# 50_Shot_CPU_V0_0.net
KiCad netlist of a schematic drawn in EAGLE
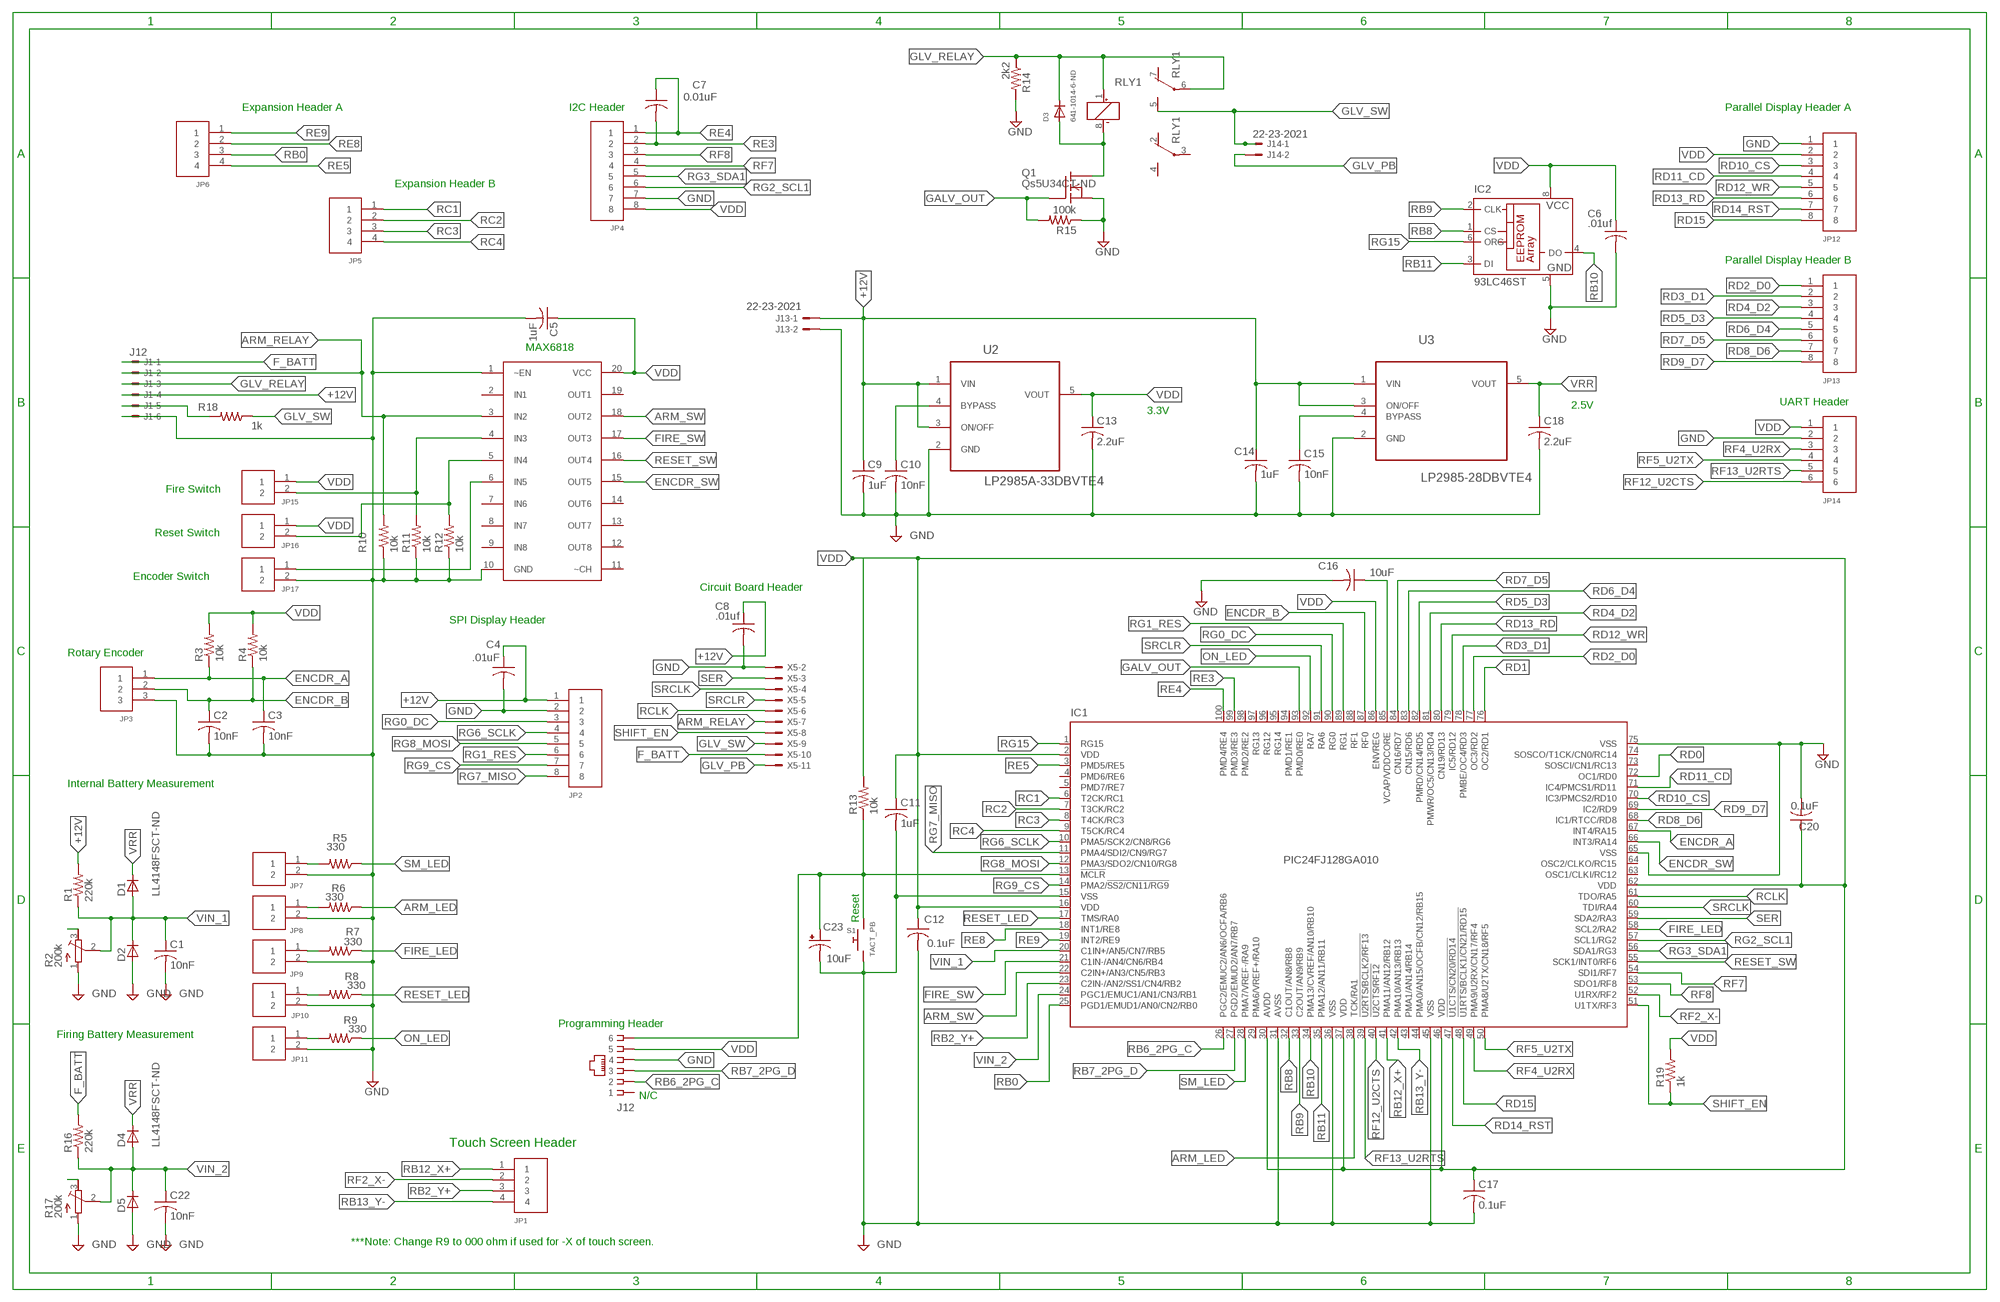
[diagram p0: schematic, sheet 1]

(export (version "E")
  (design (tool "Eeschema 10.0.6"))
  (components
    (comp (ref "C1")
      (value "10nF")
      (footprint "eagle-import:C0805")
      (libsource (lib "eagle-import") (part "C-USC0805"))
    )
    (comp (ref "C2")
      (value "10nF")
      (footprint "eagle-import:C0805")
      (libsource (lib "eagle-import") (part "C-USC0805"))
    )
    (comp (ref "C3")
      (value "10nF")
      (footprint "eagle-import:C0805")
      (libsource (lib "eagle-import") (part "C-USC0805"))
    )
    (comp (ref "C4")
      (value ".01uF")
      (footprint "eagle-import:C0805")
      (libsource (lib "eagle-import") (part "C-USC0805"))
    )
    (comp (ref "C5")
      (value "1uF")
      (footprint "eagle-import:C0805")
      (libsource (lib "eagle-import") (part "C-USC0805"))
    )
    (comp (ref "C6")
      (value ".01uf")
      (footprint "eagle-import:C0805")
      (libsource (lib "eagle-import") (part "C-USC0805"))
    )
    (comp (ref "C7")
      (value "0.01uF")
      (footprint "eagle-import:C0805")
      (libsource (lib "eagle-import") (part "C-USC0805"))
    )
    (comp (ref "C8")
      (value ".01uf")
      (footprint "eagle-import:C0805")
      (libsource (lib "eagle-import") (part "C-USC0805"))
    )
    (comp (ref "C9")
      (value "1uF")
      (footprint "eagle-import:C0805")
      (libsource (lib "eagle-import") (part "C-USC0805"))
    )
    (comp (ref "C10")
      (value "10nF")
      (footprint "eagle-import:C0805")
      (libsource (lib "eagle-import") (part "C-USC0805"))
    )
    (comp (ref "C11")
      (value "1uF")
      (footprint "eagle-import:C0805")
      (libsource (lib "eagle-import") (part "C-USC0805"))
    )
    (comp (ref "C12")
      (value "0.1uF")
      (footprint "eagle-import:C0805")
      (libsource (lib "eagle-import") (part "C-USC0805"))
    )
    (comp (ref "C13")
      (value "2.2uF")
      (footprint "eagle-import:C0805")
      (libsource (lib "eagle-import") (part "C-USC0805"))
    )
    (comp (ref "C14")
      (value "1uF")
      (footprint "eagle-import:C0805")
      (libsource (lib "eagle-import") (part "C-USC0805"))
    )
    (comp (ref "C15")
      (value "10nF")
      (footprint "eagle-import:C0805")
      (libsource (lib "eagle-import") (part "C-USC0805"))
    )
    (comp (ref "C16")
      (value "10uF")
      (footprint "eagle-import:C0805")
      (libsource (lib "eagle-import") (part "C-USC0805"))
    )
    (comp (ref "C17")
      (value "0.1uF")
      (footprint "eagle-import:C0805")
      (libsource (lib "eagle-import") (part "C-USC0805"))
    )
    (comp (ref "C18")
      (value "2.2uF")
      (footprint "eagle-import:C0805")
      (libsource (lib "eagle-import") (part "C-USC0805"))
    )
    (comp (ref "C20")
      (value "0.1uF")
      (footprint "eagle-import:C0805")
      (libsource (lib "eagle-import") (part "C-USC0805"))
    )
    (comp (ref "C22")
      (value "10nF")
      (footprint "eagle-import:C0805")
      (libsource (lib "eagle-import") (part "C-USC0805"))
    )
    (comp (ref "C23")
      (value "10uF")
      (footprint "eagle-import:CAP3X3")
      (libsource (lib "eagle-import") (part "CAP3X3"))
    )
    (comp (ref "D1")
      (value "LL4148FSCT-ND")
      (footprint "eagle-import:SOD80")
      (libsource (lib "eagle-import") (part "D-SOD-80"))
    )
    (comp (ref "D2")
      (value "LL4148FSCT-ND")
      (footprint "eagle-import:SOD80")
      (libsource (lib "eagle-import") (part "D-SOD-80"))
    )
    (comp (ref "D3")
      (value "641-1014-6-ND")
      (footprint "eagle-import:SOD-123")
      (libsource (lib "eagle-import") (part "DIODESOD-123"))
    )
    (comp (ref "D4")
      (value "LL4148FSCT-ND")
      (footprint "eagle-import:SOD80")
      (libsource (lib "eagle-import") (part "D-SOD-80"))
    )
    (comp (ref "D5")
      (value "LL4148FSCT-ND")
      (footprint "eagle-import:SOD80")
      (libsource (lib "eagle-import") (part "D-SOD-80"))
    )
    (comp (ref "IC1")
      (value "PIC24FJ128GA010")
      (footprint "eagle-import:TQFP100-14X14")
      (fields (field (name "MPN") "PIC24FJ128GA010-I/PT"))
      (libsource (lib "eagle-import") (part "PIC24FJGA010128"))
    )
    (comp (ref "IC2")
      (value "93LC46ST")
      (footprint "eagle-import:TSSOP8")
      (fields (field (name "MF") "MICROCHIP") (field (name "MPN") "93LC46C-I/ST"))
      (libsource (lib "eagle-import") (part "93STLC46"))
    )
    (comp (ref "J1")
      (value "J12")
      (footprint "eagle-import:22-23-2061")
      (fields (field (name "MF") "MOLEX") (field (name "MPN") "22-23-2061"))
      (libsource (lib "eagle-import") (part "22-23-2061"))
    )
    (comp (ref "J12")
      (value "A311422_nd")
      (footprint "eagle-import:RJ11-NO_SHIELD")
      (libsource (lib "eagle-import") (part "RJ_25"))
    )
    (comp (ref "J13")
      (value "22-23-2021")
      (footprint "eagle-import:22-23-2021")
      (fields (field (name "MF") "MOLEX"))
      (libsource (lib "eagle-import") (part "22-23-2021"))
    )
    (comp (ref "J14")
      (value "22-23-2021")
      (footprint "eagle-import:22-23-2021")
      (fields (field (name "MF") "MOLEX"))
      (libsource (lib "eagle-import") (part "22-23-2021"))
    )
    (comp (ref "JP1")
      (value "SHERLOCK_4PIN_RGT")
      (footprint "eagle-import:SHERLOCK_4PIN_RGT")
      (libsource (lib "eagle-import") (part "SHERLOCK_4PIN_RGT"))
    )
    (comp (ref "JP2")
      (value "SHERLOCK_8PIN_RGT")
      (footprint "eagle-import:SHERLOCK_8PIN-RGT")
      (libsource (lib "eagle-import") (part "SHERLOCK_8PIN_RGT"))
    )
    (comp (ref "JP3")
      (value "SHERLOCK_3PIN_RGT")
      (footprint "eagle-import:SHERLOCK_3PIN_RGT")
      (libsource (lib "eagle-import") (part "SHERLOCK_3PIN_RGT"))
    )
    (comp (ref "JP4")
      (value "SHERLOCK_8PIN_RGT")
      (footprint "eagle-import:SHERLOCK_8PIN-RGT")
      (libsource (lib "eagle-import") (part "SHERLOCK_8PIN_RGT"))
    )
    (comp (ref "JP5")
      (value "SHERLOCK_4PIN_RGT")
      (footprint "eagle-import:SHERLOCK_4PIN_RGT")
      (libsource (lib "eagle-import") (part "SHERLOCK_4PIN_RGT"))
    )
    (comp (ref "JP6")
      (value "SHERLOCK_4PIN_RGT")
      (footprint "eagle-import:SHERLOCK_4PIN_RGT")
      (libsource (lib "eagle-import") (part "SHERLOCK_4PIN_RGT"))
    )
    (comp (ref "JP7")
      (value "SHERLOCK_2PIN_RGT")
      (footprint "eagle-import:SHERLOCK_2PIN_RGT")
      (libsource (lib "eagle-import") (part "SHERLOCK_2PIN_RGT"))
    )
    (comp (ref "JP8")
      (value "SHERLOCK_2PIN_RGT")
      (footprint "eagle-import:SHERLOCK_2PIN_RGT")
      (libsource (lib "eagle-import") (part "SHERLOCK_2PIN_RGT"))
    )
    (comp (ref "JP9")
      (value "SHERLOCK_2PIN_RGT")
      (footprint "eagle-import:SHERLOCK_2PIN_RGT")
      (libsource (lib "eagle-import") (part "SHERLOCK_2PIN_RGT"))
    )
    (comp (ref "JP10")
      (value "SHERLOCK_2PIN_RGT")
      (footprint "eagle-import:SHERLOCK_2PIN_RGT")
      (libsource (lib "eagle-import") (part "SHERLOCK_2PIN_RGT"))
    )
    (comp (ref "JP11")
      (value "SHERLOCK_2PIN_RGT")
      (footprint "eagle-import:SHERLOCK_2PIN_RGT")
      (libsource (lib "eagle-import") (part "SHERLOCK_2PIN_RGT"))
    )
    (comp (ref "JP12")
      (value "SHERLOCK_8PIN_RGT")
      (footprint "eagle-import:SHERLOCK_8PIN-RGT")
      (libsource (lib "eagle-import") (part "SHERLOCK_8PIN_RGT"))
    )
    (comp (ref "JP13")
      (value "SHERLOCK_8PIN_RGT")
      (footprint "eagle-import:SHERLOCK_8PIN-RGT")
      (libsource (lib "eagle-import") (part "SHERLOCK_8PIN_RGT"))
    )
    (comp (ref "JP14")
      (value "SHERLOCK_6PIN_RGT")
      (footprint "eagle-import:SHERLOCK_6PIN_RGT")
      (libsource (lib "eagle-import") (part "SHERLOCK_6PIN_RGT"))
    )
    (comp (ref "JP15")
      (value "SHERLOCK_2PIN_RGT")
      (footprint "eagle-import:SHERLOCK_2PIN_RGT")
      (libsource (lib "eagle-import") (part "SHERLOCK_2PIN_RGT"))
    )
    (comp (ref "JP16")
      (value "SHERLOCK_2PIN_RGT")
      (footprint "eagle-import:SHERLOCK_2PIN_RGT")
      (libsource (lib "eagle-import") (part "SHERLOCK_2PIN_RGT"))
    )
    (comp (ref "JP17")
      (value "SHERLOCK_2PIN_RGT")
      (footprint "eagle-import:SHERLOCK_2PIN_RGT")
      (libsource (lib "eagle-import") (part "SHERLOCK_2PIN_RGT"))
    )
    (comp (ref "Q1")
      (value "Qs5U34CT-ND")
      (footprint "eagle-import:SOT23-5L")
      (libsource (lib "eagle-import") (part "QS5U34CT-ND_MOSFET_N_CHANNEL"))
    )
    (comp (ref "R1")
      (value "220k")
      (footprint "eagle-import:M0805")
      (libsource (lib "eagle-import") (part "R-US_M0805"))
    )
    (comp (ref "R2")
      (value "200k")
      (footprint "eagle-import:RTRIM3224X")
      (libsource (lib "eagle-import") (part "R-TRIMM3224X"))
    )
    (comp (ref "R3")
      (value "10k")
      (footprint "eagle-import:M0805")
      (libsource (lib "eagle-import") (part "R-US_M0805"))
    )
    (comp (ref "R4")
      (value "10k")
      (footprint "eagle-import:M0805")
      (libsource (lib "eagle-import") (part "R-US_M0805"))
    )
    (comp (ref "R5")
      (value "330")
      (footprint "eagle-import:M0805")
      (libsource (lib "eagle-import") (part "R-US_M0805"))
    )
    (comp (ref "R6")
      (value "330")
      (footprint "eagle-import:M0805")
      (libsource (lib "eagle-import") (part "R-US_M0805"))
    )
    (comp (ref "R7")
      (value "330")
      (footprint "eagle-import:M0805")
      (libsource (lib "eagle-import") (part "R-US_M0805"))
    )
    (comp (ref "R8")
      (value "330")
      (footprint "eagle-import:M0805")
      (libsource (lib "eagle-import") (part "R-US_M0805"))
    )
    (comp (ref "R9")
      (value "330")
      (footprint "eagle-import:M0805")
      (libsource (lib "eagle-import") (part "R-US_M0805"))
    )
    (comp (ref "R10")
      (value "10k")
      (footprint "eagle-import:M0805")
      (libsource (lib "eagle-import") (part "R-US_M0805"))
    )
    (comp (ref "R11")
      (value "10k")
      (footprint "eagle-import:M0805")
      (libsource (lib "eagle-import") (part "R-US_M0805"))
    )
    (comp (ref "R12")
      (value "10k")
      (footprint "eagle-import:M0805")
      (libsource (lib "eagle-import") (part "R-US_M0805"))
    )
    (comp (ref "R13")
      (value "10k")
      (footprint "eagle-import:M0805")
      (libsource (lib "eagle-import") (part "rcl-2_R-US_M0805"))
    )
    (comp (ref "R14")
      (value "2k2")
      (footprint "eagle-import:M0805")
      (libsource (lib "eagle-import") (part "R-US_M0805"))
    )
    (comp (ref "R15")
      (value "100k")
      (footprint "eagle-import:M0805")
      (libsource (lib "eagle-import") (part "R-US_M0805"))
    )
    (comp (ref "R16")
      (value "220k")
      (footprint "eagle-import:M0805")
      (libsource (lib "eagle-import") (part "R-US_M0805"))
    )
    (comp (ref "R17")
      (value "200k")
      (footprint "eagle-import:RTRIM3224X")
      (libsource (lib "eagle-import") (part "R-TRIMM3224X"))
    )
    (comp (ref "R18")
      (value "1k")
      (footprint "eagle-import:M0805")
      (libsource (lib "eagle-import") (part "R-US_M0805"))
    )
    (comp (ref "R19")
      (value "1k")
      (footprint "eagle-import:M0805")
      (libsource (lib "eagle-import") (part "rcl-2_R-US_M0805"))
    )
    (comp (ref "RLY1")
      (value "OMRON")
      (footprint "eagle-import:OMRONG6S")
      (libsource (lib "eagle-import") (part "OMRON"))
    )
    (comp (ref "S1")
      (value "TACT_PB")
      (footprint "eagle-import:PUSHBUTTON_SMD_SJ")
      (libsource (lib "eagle-import") (part "TACT_PB"))
    )
    (comp (ref "U1")
      (value "MAX6818")
      (footprint "eagle-import:SSOP20")
      (libsource (lib "eagle-import") (part "MAX6818"))
    )
    (comp (ref "U2")
      (value "LP2985A-33DBVTE4")
      (footprint "eagle-import:SOT95P280X145-5N")
      (libsource (lib "eagle-import") (part "LP2985A-33DBVTE4"))
    )
    (comp (ref "U3")
      (value "LP2985-28DBVTE4")
      (footprint "eagle-import:SOT95P280X145-5N")
      (libsource (lib "eagle-import") (part "LP2985-28DBVTE4"))
    )
    (comp (ref "X5")
      (value "22-23-2111")
      (footprint "eagle-import:22-23-2111")
      (fields (field (name "MF") "MOLEX"))
      (libsource (lib "eagle-import") (part "22-23-2111"))
    )
  )
  (nets
    (net (code "1") (name "+12V") (class "Default")
      (node (ref "C14") (pin "1") (pinfunction "1_1") (pintype "passive"))
      (node (ref "C4") (pin "1") (pinfunction "1_1") (pintype "passive"))
      (node (ref "C8") (pin "1") (pinfunction "1_1") (pintype "passive"))
      (node (ref "C9") (pin "1") (pinfunction "1_1") (pintype "passive"))
      (node (ref "J1") (pin "4") (pinfunction "S_4") (pintype "passive"))
      (node (ref "J13") (pin "1") (pinfunction "S_1") (pintype "passive"))
      (node (ref "JP2") (pin "1") (pinfunction "1_1") (pintype "bidirectional"))
      (node (ref "R1") (pin "2") (pinfunction "2_2") (pintype "passive"))
      (node (ref "U2") (pin "1") (pinfunction "VIN_1") (pintype "power_in"))
      (node (ref "U2") (pin "3") (pinfunction "ON/OFF_3") (pintype "input"))
      (node (ref "U3") (pin "1") (pinfunction "VIN_1") (pintype "power_in"))
      (node (ref "U3") (pin "3") (pinfunction "ON/OFF_3") (pintype "input"))
    )
    (net (code "2") (name "ARM_LED") (class "Default")
      (node (ref "IC1") (pin "38") (pinfunction "TCK/RA1_38") (pintype "bidirectional"))
      (node (ref "R6") (pin "1") (pinfunction "1_1") (pintype "passive"))
    )
    (net (code "3") (name "ARM_RELAY") (class "Default")
      (node (ref "J1") (pin "2") (pinfunction "S_2") (pintype "passive"))
      (node (ref "R10") (pin "2") (pinfunction "2_2") (pintype "passive"))
      (node (ref "U1") (pin "3") (pinfunction "IN2_3") (pintype "bidirectional"))
      (node (ref "X5") (pin "7") (pinfunction "S_7") (pintype "passive"))
    )
    (net (code "4") (name "ARM_SW") (class "Default")
      (node (ref "IC1") (pin "22") (pinfunction "C2IN+/AN3/CN5/RB3_22") (pintype "bidirectional"))
      (node (ref "U1") (pin "18") (pinfunction "OUT2_18") (pintype "output"))
    )
    (net (code "5") (name "ENCDR_A") (class "Default")
      (node (ref "C3") (pin "1") (pinfunction "1_1") (pintype "passive"))
      (node (ref "IC1") (pin "67") (pinfunction "INT4/RA15_67") (pintype "bidirectional"))
      (node (ref "JP3") (pin "1") (pinfunction "1_1") (pintype "bidirectional"))
      (node (ref "R3") (pin "1") (pinfunction "1_1") (pintype "passive"))
    )
    (net (code "6") (name "ENCDR_B") (class "Default")
      (node (ref "C2") (pin "1") (pinfunction "1_1") (pintype "passive"))
      (node (ref "IC1") (pin "87") (pinfunction "RF0_87") (pintype "bidirectional"))
      (node (ref "JP3") (pin "2") (pinfunction "2_2") (pintype "bidirectional"))
      (node (ref "R4") (pin "1") (pinfunction "1_1") (pintype "passive"))
    )
    (net (code "7") (name "ENCDR_SW") (class "Default")
      (node (ref "IC1") (pin "66") (pinfunction "INT3/RA14_66") (pintype "bidirectional"))
      (node (ref "U1") (pin "15") (pinfunction "OUT5_15") (pintype "output"))
    )
    (net (code "8") (name "FIRE_LED") (class "Default")
      (node (ref "IC1") (pin "58") (pinfunction "SCL2/RA2_58") (pintype "bidirectional"))
      (node (ref "R7") (pin "1") (pinfunction "1_1") (pintype "passive"))
    )
    (net (code "9") (name "FIRE_SW") (class "Default")
      (node (ref "IC1") (pin "21") (pinfunction "C1IN-/AN4/CN6/RB4_21") (pintype "bidirectional"))
      (node (ref "U1") (pin "17") (pinfunction "OUT3_17") (pintype "output"))
    )
    (net (code "10") (name "F_BATT") (class "Default")
      (node (ref "J1") (pin "1") (pinfunction "S_1") (pintype "passive"))
      (node (ref "R16") (pin "2") (pinfunction "2_2") (pintype "passive"))
      (node (ref "X5") (pin "10") (pinfunction "S_10") (pintype "passive"))
    )
    (net (code "11") (name "GALV_OUT") (class "Default")
      (node (ref "IC1") (pin "93") (pinfunction "PMD0/RE0_93") (pintype "bidirectional"))
      (node (ref "Q1") (pin "1") (pinfunction "G_1") (pintype "passive"))
      (node (ref "R15") (pin "2") (pinfunction "2_2") (pintype "passive"))
    )
    (net (code "12") (name "GLV_PB") (class "Default")
      (node (ref "J14") (pin "2") (pinfunction "S_2") (pintype "passive"))
      (node (ref "X5") (pin "11") (pinfunction "S_11") (pintype "passive"))
    )
    (net (code "13") (name "GLV_RELAY") (class "Default")
      (node (ref "D3") (pin "C") (pinfunction "C_C") (pintype "passive"))
      (node (ref "J1") (pin "3") (pinfunction "S_3") (pintype "passive"))
      (node (ref "R14") (pin "1") (pinfunction "1_1") (pintype "passive"))
      (node (ref "RLY1") (pin "1") (pinfunction "+_1") (pintype "passive"))
      (node (ref "RLY1") (pin "6") (pinfunction "P_6") (pintype "passive"))
    )
    (net (code "14") (name "GLV_SW") (class "Default")
      (node (ref "J14") (pin "1") (pinfunction "S_1") (pintype "passive"))
      (node (ref "R18") (pin "1") (pinfunction "1_1") (pintype "passive"))
      (node (ref "RLY1") (pin "5") (pinfunction "S_5") (pintype "passive"))
      (node (ref "X5") (pin "9") (pinfunction "S_9") (pintype "passive"))
    )
    (net (code "15") (name "GND") (class "Default")
      (node (ref "C1") (pin "2") (pinfunction "2_2") (pintype "passive"))
      (node (ref "C10") (pin "2") (pinfunction "2_2") (pintype "passive"))
      (node (ref "C11") (pin "2") (pinfunction "2_2") (pintype "passive"))
      (node (ref "C12") (pin "2") (pinfunction "2_2") (pintype "passive"))
      (node (ref "C13") (pin "2") (pinfunction "2_2") (pintype "passive"))
      (node (ref "C14") (pin "2") (pinfunction "2_2") (pintype "passive"))
      (node (ref "C15") (pin "2") (pinfunction "2_2") (pintype "passive"))
      (node (ref "C16") (pin "2") (pinfunction "2_2") (pintype "passive"))
      (node (ref "C17") (pin "2") (pinfunction "2_2") (pintype "passive"))
      (node (ref "C18") (pin "2") (pinfunction "2_2") (pintype "passive"))
      (node (ref "C2") (pin "2") (pinfunction "2_2") (pintype "passive"))
      (node (ref "C20") (pin "2") (pinfunction "2_2") (pintype "passive"))
      (node (ref "C22") (pin "2") (pinfunction "2_2") (pintype "passive"))
      (node (ref "C23") (pin "-") (pinfunction "-_-") (pintype "passive"))
      (node (ref "C3") (pin "2") (pinfunction "2_2") (pintype "passive"))
      (node (ref "C4") (pin "2") (pinfunction "2_2") (pintype "passive"))
      (node (ref "C5") (pin "2") (pinfunction "2_2") (pintype "passive"))
      (node (ref "C6") (pin "2") (pinfunction "2_2") (pintype "passive"))
      (node (ref "C8") (pin "2") (pinfunction "2_2") (pintype "passive"))
      (node (ref "C9") (pin "2") (pinfunction "2_2") (pintype "passive"))
      (node (ref "D2") (pin "2") (pinfunction "A_2") (pintype "passive"))
      (node (ref "D5") (pin "2") (pinfunction "A_2") (pintype "passive"))
      (node (ref "IC1") (pin "15") (pinfunction "VSS_15") (pintype "power_in"))
      (node (ref "IC1") (pin "31") (pinfunction "AVSS_31") (pintype "power_in"))
      (node (ref "IC1") (pin "36") (pinfunction "VSS_36") (pintype "power_in"))
      (node (ref "IC1") (pin "45") (pinfunction "VSS_45") (pintype "power_in"))
      (node (ref "IC1") (pin "65") (pinfunction "VSS_65") (pintype "power_in"))
      (node (ref "IC1") (pin "75") (pinfunction "VSS_75") (pintype "power_in"))
      (node (ref "IC2") (pin "5") (pinfunction "GND_5") (pintype "power_in"))
      (node (ref "J1") (pin "6") (pinfunction "S_6") (pintype "passive"))
      (node (ref "J12") (pin "4") (pinfunction "4_4") (pintype "passive"))
      (node (ref "J13") (pin "2") (pinfunction "S_2") (pintype "passive"))
      (node (ref "JP10") (pin "2") (pinfunction "2_2") (pintype "bidirectional"))
      (node (ref "JP11") (pin "2") (pinfunction "2_2") (pintype "bidirectional"))
      (node (ref "JP12") (pin "1") (pinfunction "1_1") (pintype "bidirectional"))
      (node (ref "JP14") (pin "2") (pinfunction "2_2") (pintype "bidirectional"))
      (node (ref "JP17") (pin "2") (pinfunction "2_2") (pintype "bidirectional"))
      (node (ref "JP2") (pin "2") (pinfunction "2_2") (pintype "bidirectional"))
      (node (ref "JP3") (pin "3") (pinfunction "3_3") (pintype "bidirectional"))
      (node (ref "JP4") (pin "7") (pinfunction "7_7") (pintype "bidirectional"))
      (node (ref "JP7") (pin "2") (pinfunction "2_2") (pintype "bidirectional"))
      (node (ref "JP8") (pin "2") (pinfunction "2_2") (pintype "bidirectional"))
      (node (ref "JP9") (pin "2") (pinfunction "2_2") (pintype "bidirectional"))
      (node (ref "Q1") (pin "2") (pinfunction "S_2") (pintype "passive"))
      (node (ref "R10") (pin "1") (pinfunction "1_1") (pintype "passive"))
      (node (ref "R11") (pin "1") (pinfunction "1_1") (pintype "passive"))
      (node (ref "R12") (pin "1") (pinfunction "1_1") (pintype "passive"))
      (node (ref "R14") (pin "2") (pinfunction "2_2") (pintype "passive"))
      (node (ref "R15") (pin "1") (pinfunction "1_1") (pintype "passive"))
      (node (ref "R17") (pin "1") (pinfunction "A_1") (pintype "passive"))
      (node (ref "R2") (pin "1") (pinfunction "A_1") (pintype "passive"))
      (node (ref "S1") (pin "1") (pinfunction "1_1") (pintype "passive"))
      (node (ref "S1") (pin "2") (pinfunction "1_2") (pintype "passive"))
      (node (ref "U1") (pin "1") (pinfunction "~{EN}_1") (pintype "bidirectional"))
      (node (ref "U1") (pin "10") (pinfunction "GND_10") (pintype "power_in"))
      (node (ref "U2") (pin "2") (pinfunction "GND_2") (pintype "passive"))
      (node (ref "U3") (pin "2") (pinfunction "GND_2") (pintype "passive"))
      (node (ref "X5") (pin "2") (pinfunction "S_2") (pintype "passive"))
    )
    (net (code "16") (name "Net-(IC1-VCAP{slash}VDDCORE)") (class "Default")
      (node (ref "C16") (pin "1") (pinfunction "1_1") (pintype "passive"))
      (node (ref "IC1") (pin "85") (pinfunction "VCAP/VDDCORE_85") (pintype "bidirectional"))
    )
    (net (code "17") (name "Net-(IC1-~{MCLR})") (class "Default")
      (node (ref "C23") (pin "+") (pinfunction "+_+") (pintype "passive"))
      (node (ref "IC1") (pin "13") (pinfunction "~{MCLR}_13") (pintype "bidirectional"))
      (node (ref "J12") (pin "6") (pinfunction "6_6") (pintype "passive"))
      (node (ref "R13") (pin "1") (pinfunction "1_1") (pintype "passive"))
      (node (ref "S1") (pin "3") (pinfunction "2_3") (pintype "passive"))
      (node (ref "S1") (pin "4") (pinfunction "2_4") (pintype "passive"))
    )
    (net (code "18") (name "Net-(J1E-S)") (class "Default")
      (node (ref "J1") (pin "5") (pinfunction "S_5") (pintype "passive"))
      (node (ref "R18") (pin "2") (pinfunction "2_2") (pintype "passive"))
    )
    (net (code "19") (name "Net-(JP7-Pad1)") (class "Default")
      (node (ref "JP7") (pin "1") (pinfunction "1_1") (pintype "bidirectional"))
      (node (ref "R5") (pin "2") (pinfunction "2_2") (pintype "passive"))
    )
    (net (code "20") (name "Net-(JP8-Pad1)") (class "Default")
      (node (ref "JP8") (pin "1") (pinfunction "1_1") (pintype "bidirectional"))
      (node (ref "R6") (pin "2") (pinfunction "2_2") (pintype "passive"))
    )
    (net (code "21") (name "Net-(JP9-Pad1)") (class "Default")
      (node (ref "JP9") (pin "1") (pinfunction "1_1") (pintype "bidirectional"))
      (node (ref "R7") (pin "2") (pinfunction "2_2") (pintype "passive"))
    )
    (net (code "22") (name "Net-(JP10-Pad1)") (class "Default")
      (node (ref "JP10") (pin "1") (pinfunction "1_1") (pintype "bidirectional"))
      (node (ref "R8") (pin "2") (pinfunction "2_2") (pintype "passive"))
    )
    (net (code "23") (name "Net-(JP11-Pad1)") (class "Default")
      (node (ref "JP11") (pin "1") (pinfunction "1_1") (pintype "bidirectional"))
      (node (ref "R9") (pin "2") (pinfunction "2_2") (pintype "passive"))
    )
    (net (code "24") (name "Net-(Q1-D)") (class "Default")
      (node (ref "D3") (pin "A") (pinfunction "A_A") (pintype "passive"))
      (node (ref "Q1") (pin "5") (pinfunction "D_5") (pintype "passive"))
      (node (ref "RLY1") (pin "8") (pinfunction "-_8") (pintype "passive"))
    )
    (net (code "25") (name "Net-(U1-IN3)") (class "Default")
      (node (ref "JP15") (pin "2") (pinfunction "2_2") (pintype "bidirectional"))
      (node (ref "R11") (pin "2") (pinfunction "2_2") (pintype "passive"))
      (node (ref "U1") (pin "4") (pinfunction "IN3_4") (pintype "bidirectional"))
    )
    (net (code "26") (name "Net-(U1-IN4)") (class "Default")
      (node (ref "JP16") (pin "2") (pinfunction "2_2") (pintype "bidirectional"))
      (node (ref "R12") (pin "2") (pinfunction "2_2") (pintype "passive"))
      (node (ref "U1") (pin "5") (pinfunction "IN4_5") (pintype "bidirectional"))
    )
    (net (code "27") (name "Net-(U1-IN5)") (class "Default")
      (node (ref "JP17") (pin "1") (pinfunction "1_1") (pintype "bidirectional"))
      (node (ref "U1") (pin "6") (pinfunction "IN5_6") (pintype "bidirectional"))
    )
    (net (code "28") (name "Net-(U2-BYPASS)") (class "Default")
      (node (ref "C10") (pin "1") (pinfunction "1_1") (pintype "passive"))
      (node (ref "U2") (pin "4") (pinfunction "BYPASS_4") (pintype "input"))
    )
    (net (code "29") (name "Net-(U3-BYPASS)") (class "Default")
      (node (ref "C15") (pin "1") (pinfunction "1_1") (pintype "passive"))
      (node (ref "U3") (pin "4") (pinfunction "BYPASS_4") (pintype "input"))
    )
    (net (code "30") (name "ON_LED") (class "Default")
      (node (ref "IC1") (pin "92") (pinfunction "RA7_92") (pintype "bidirectional"))
      (node (ref "R9") (pin "1") (pinfunction "1_1") (pintype "passive"))
    )
    (net (code "31") (name "RB0") (class "Default")
      (node (ref "IC1") (pin "25") (pinfunction "PGD1/EMUD1/AN0/CN2/RB0_25") (pintype "bidirectional"))
      (node (ref "JP6") (pin "3") (pinfunction "3_3") (pintype "bidirectional"))
    )
    (net (code "32") (name "RB2_Y+") (class "Default")
      (node (ref "IC1") (pin "23") (pinfunction "C2IN-/AN2/SS1/CN4/RB2_23") (pintype "bidirectional"))
      (node (ref "JP1") (pin "3") (pinfunction "3_3") (pintype "bidirectional"))
    )
    (net (code "33") (name "RB6_2PG_C") (class "Default")
      (node (ref "IC1") (pin "26") (pinfunction "PGC2/EMUC2/AN6/OCFA/RB6_26") (pintype "bidirectional"))
      (node (ref "J12") (pin "2") (pinfunction "2_2") (pintype "passive"))
    )
    (net (code "34") (name "RB7_2PG_D") (class "Default")
      (node (ref "IC1") (pin "27") (pinfunction "PGD2/EMUD2/AN7/RB7_27") (pintype "bidirectional"))
      (node (ref "J12") (pin "3") (pinfunction "3_3") (pintype "passive"))
    )
    (net (code "35") (name "RB8") (class "Default")
      (node (ref "IC1") (pin "32") (pinfunction "C1OUT/AN8/RB8_32") (pintype "bidirectional"))
      (node (ref "IC2") (pin "1") (pinfunction "CS_1") (pintype "input"))
    )
    (net (code "36") (name "RB9") (class "Default")
      (node (ref "IC1") (pin "33") (pinfunction "C2OUT/AN9/RB9_33") (pintype "bidirectional"))
      (node (ref "IC2") (pin "2") (pinfunction "CLK_2") (pintype "input"))
    )
    (net (code "37") (name "RB10") (class "Default")
      (node (ref "IC1") (pin "34") (pinfunction "PMA13/CVREF/AN10/RB10_34") (pintype "bidirectional"))
      (node (ref "IC2") (pin "4") (pinfunction "DO_4") (pintype "tri_state"))
    )
    (net (code "38") (name "RB11") (class "Default")
      (node (ref "IC1") (pin "35") (pinfunction "PMA12/AN11/RB11_35") (pintype "bidirectional"))
      (node (ref "IC2") (pin "3") (pinfunction "DI_3") (pintype "input"))
    )
    (net (code "39") (name "RB12_X+") (class "Default")
      (node (ref "IC1") (pin "41") (pinfunction "PMA11/AN12/RB12_41") (pintype "bidirectional"))
      (node (ref "JP1") (pin "1") (pinfunction "1_1") (pintype "bidirectional"))
    )
    (net (code "40") (name "RB13_Y-") (class "Default")
      (node (ref "IC1") (pin "42") (pinfunction "PMA10/AN13/RB13_42") (pintype "bidirectional"))
      (node (ref "JP1") (pin "4") (pinfunction "4_4") (pintype "bidirectional"))
    )
    (net (code "41") (name "RC1") (class "Default")
      (node (ref "IC1") (pin "6") (pinfunction "T2CK/RC1_6") (pintype "bidirectional"))
      (node (ref "JP5") (pin "1") (pinfunction "1_1") (pintype "bidirectional"))
    )
    (net (code "42") (name "RC2") (class "Default")
      (node (ref "IC1") (pin "7") (pinfunction "T3CK/RC2_7") (pintype "bidirectional"))
      (node (ref "JP5") (pin "2") (pinfunction "2_2") (pintype "bidirectional"))
    )
    (net (code "43") (name "RC3") (class "Default")
      (node (ref "IC1") (pin "8") (pinfunction "T4CK/RC3_8") (pintype "bidirectional"))
      (node (ref "JP5") (pin "3") (pinfunction "3_3") (pintype "bidirectional"))
    )
    (net (code "44") (name "RC4") (class "Default")
      (node (ref "IC1") (pin "9") (pinfunction "T5CK/RC4_9") (pintype "bidirectional"))
      (node (ref "JP5") (pin "4") (pinfunction "4_4") (pintype "bidirectional"))
    )
    (net (code "45") (name "RCLK") (class "Default")
      (node (ref "IC1") (pin "61") (pinfunction "TDO/RA5_61") (pintype "bidirectional"))
      (node (ref "X5") (pin "6") (pinfunction "S_6") (pintype "passive"))
    )
    (net (code "46") (name "RD0") (class "Default")
      (node (ref "IC1") (pin "72") (pinfunction "OC1/RD0_72") (pintype "bidirectional"))
    )
    (net (code "47") (name "RD1") (class "Default")
      (node (ref "IC1") (pin "76") (pinfunction "OC2/RD1_76") (pintype "bidirectional"))
    )
    (net (code "48") (name "RD2_D0") (class "Default")
      (node (ref "IC1") (pin "77") (pinfunction "OC3/RD2_77") (pintype "bidirectional"))
      (node (ref "JP13") (pin "1") (pinfunction "1_1") (pintype "bidirectional"))
    )
    (net (code "49") (name "RD3_D1") (class "Default")
      (node (ref "IC1") (pin "78") (pinfunction "PMBE/OC4/RD3_78") (pintype "bidirectional"))
      (node (ref "JP13") (pin "2") (pinfunction "2_2") (pintype "bidirectional"))
    )
    (net (code "50") (name "RD4_D2") (class "Default")
      (node (ref "IC1") (pin "81") (pinfunction "PMWR/OC5/CN13/RD4_81") (pintype "bidirectional"))
      (node (ref "JP13") (pin "3") (pinfunction "3_3") (pintype "bidirectional"))
    )
    (net (code "51") (name "RD5_D3") (class "Default")
      (node (ref "IC1") (pin "82") (pinfunction "PMRD/CN14/RD5_82") (pintype "bidirectional"))
      (node (ref "JP13") (pin "4") (pinfunction "4_4") (pintype "bidirectional"))
    )
    (net (code "52") (name "RD6_D4") (class "Default")
      (node (ref "IC1") (pin "83") (pinfunction "CN15/RD6_83") (pintype "bidirectional"))
      (node (ref "JP13") (pin "5") (pinfunction "5_5") (pintype "bidirectional"))
    )
    (net (code "53") (name "RD7_D5") (class "Default")
      (node (ref "IC1") (pin "84") (pinfunction "CN16/RD7_84") (pintype "bidirectional"))
      (node (ref "JP13") (pin "6") (pinfunction "6_6") (pintype "bidirectional"))
    )
    (net (code "54") (name "RD8_D6") (class "Default")
      (node (ref "IC1") (pin "68") (pinfunction "IC1/RTCC/RD8_68") (pintype "bidirectional"))
      (node (ref "JP13") (pin "7") (pinfunction "7_7") (pintype "bidirectional"))
    )
    (net (code "55") (name "RD9_D7") (class "Default")
      (node (ref "IC1") (pin "69") (pinfunction "IC2/RD9_69") (pintype "bidirectional"))
      (node (ref "JP13") (pin "8") (pinfunction "8_8") (pintype "bidirectional"))
    )
    (net (code "56") (name "RD10_CS") (class "Default")
      (node (ref "IC1") (pin "70") (pinfunction "IC3/PMCS2/RD10_70") (pintype "bidirectional"))
      (node (ref "JP12") (pin "3") (pinfunction "3_3") (pintype "bidirectional"))
    )
    (net (code "57") (name "RD11_CD") (class "Default")
      (node (ref "IC1") (pin "71") (pinfunction "IC4/PMCS1/RD11_71") (pintype "bidirectional"))
      (node (ref "JP12") (pin "4") (pinfunction "4_4") (pintype "bidirectional"))
    )
    (net (code "58") (name "RD12_WR") (class "Default")
      (node (ref "IC1") (pin "79") (pinfunction "IC5/RD12_79") (pintype "bidirectional"))
      (node (ref "JP12") (pin "5") (pinfunction "5_5") (pintype "bidirectional"))
    )
    (net (code "59") (name "RD13_RD") (class "Default")
      (node (ref "IC1") (pin "80") (pinfunction "CN19/RD13_80") (pintype "bidirectional"))
      (node (ref "JP12") (pin "6") (pinfunction "6_6") (pintype "bidirectional"))
    )
    (net (code "60") (name "RD14_RST") (class "Default")
      (node (ref "IC1") (pin "47") (pinfunction "~{U1CTS/CN20/RD14}_47") (pintype "bidirectional"))
      (node (ref "JP12") (pin "7") (pinfunction "7_7") (pintype "bidirectional"))
    )
    (net (code "61") (name "RD15") (class "Default")
      (node (ref "IC1") (pin "48") (pinfunction "~{U1RTS/BCLK1/CN21/RD15}_48") (pintype "bidirectional"))
      (node (ref "JP12") (pin "8") (pinfunction "8_8") (pintype "bidirectional"))
    )
    (net (code "62") (name "RE3") (class "Default")
      (node (ref "C7") (pin "2") (pinfunction "2_2") (pintype "passive"))
      (node (ref "IC1") (pin "99") (pinfunction "PMD3/RE3_99") (pintype "bidirectional"))
      (node (ref "JP4") (pin "2") (pinfunction "2_2") (pintype "bidirectional"))
    )
    (net (code "63") (name "RE4") (class "Default")
      (node (ref "C7") (pin "1") (pinfunction "1_1") (pintype "passive"))
      (node (ref "IC1") (pin "100") (pinfunction "PMD4/RE4_100") (pintype "bidirectional"))
      (node (ref "JP4") (pin "1") (pinfunction "1_1") (pintype "bidirectional"))
    )
    (net (code "64") (name "RE5") (class "Default")
      (node (ref "IC1") (pin "3") (pinfunction "PMD5/RE5_3") (pintype "bidirectional"))
      (node (ref "JP6") (pin "4") (pinfunction "4_4") (pintype "bidirectional"))
    )
    (net (code "65") (name "RE8") (class "Default")
      (node (ref "IC1") (pin "18") (pinfunction "INT1/RE8_18") (pintype "bidirectional"))
      (node (ref "JP6") (pin "2") (pinfunction "2_2") (pintype "bidirectional"))
    )
    (net (code "66") (name "RE9") (class "Default")
      (node (ref "IC1") (pin "19") (pinfunction "INT2/RE9_19") (pintype "bidirectional"))
      (node (ref "JP6") (pin "1") (pinfunction "1_1") (pintype "bidirectional"))
    )
    (net (code "67") (name "RESET_LED") (class "Default")
      (node (ref "IC1") (pin "17") (pinfunction "TMS/RA0_17") (pintype "bidirectional"))
      (node (ref "R8") (pin "1") (pinfunction "1_1") (pintype "passive"))
    )
    (net (code "68") (name "RESET_SW") (class "Default")
      (node (ref "IC1") (pin "55") (pinfunction "SCK1/INT0/RF6_55") (pintype "bidirectional"))
      (node (ref "U1") (pin "16") (pinfunction "OUT4_16") (pintype "output"))
    )
    (net (code "69") (name "RF2_X-") (class "Default")
      (node (ref "IC1") (pin "52") (pinfunction "U1RX/RF2_52") (pintype "bidirectional"))
      (node (ref "JP1") (pin "2") (pinfunction "2_2") (pintype "bidirectional"))
    )
    (net (code "70") (name "RF4_U2RX") (class "Default")
      (node (ref "IC1") (pin "49") (pinfunction "PMA9/U2RX/CN17/RF4_49") (pintype "bidirectional"))
      (node (ref "JP14") (pin "3") (pinfunction "3_3") (pintype "bidirectional"))
    )
    (net (code "71") (name "RF5_U2TX") (class "Default")
      (node (ref "IC1") (pin "50") (pinfunction "PMA8/U2TX/CN18/RF5_50") (pintype "bidirectional"))
      (node (ref "JP14") (pin "4") (pinfunction "4_4") (pintype "bidirectional"))
    )
    (net (code "72") (name "RF7") (class "Default")
      (node (ref "IC1") (pin "54") (pinfunction "SDI1/RF7_54") (pintype "bidirectional"))
      (node (ref "JP4") (pin "4") (pinfunction "4_4") (pintype "bidirectional"))
    )
    (net (code "73") (name "RF8") (class "Default")
      (node (ref "IC1") (pin "53") (pinfunction "SDO1/RF8_53") (pintype "bidirectional"))
      (node (ref "JP4") (pin "3") (pinfunction "3_3") (pintype "bidirectional"))
    )
    (net (code "74") (name "RF12_U2CTS") (class "Default")
      (node (ref "IC1") (pin "40") (pinfunction "~{U2CTS/RF12}_40") (pintype "bidirectional"))
      (node (ref "JP14") (pin "6") (pinfunction "6_6") (pintype "bidirectional"))
    )
    (net (code "75") (name "RF13_U2RTS") (class "Default")
      (node (ref "IC1") (pin "39") (pinfunction "~{U2RTS/BCLK2/RF13}_39") (pintype "bidirectional"))
      (node (ref "JP14") (pin "5") (pinfunction "5_5") (pintype "bidirectional"))
    )
    (net (code "76") (name "RG0_DC") (class "Default")
      (node (ref "IC1") (pin "90") (pinfunction "RG0_90") (pintype "bidirectional"))
      (node (ref "JP2") (pin "3") (pinfunction "3_3") (pintype "bidirectional"))
    )
    (net (code "77") (name "RG1_RES") (class "Default")
      (node (ref "IC1") (pin "89") (pinfunction "RG1_89") (pintype "bidirectional"))
      (node (ref "JP2") (pin "6") (pinfunction "6_6") (pintype "bidirectional"))
    )
    (net (code "78") (name "RG2_SCL1") (class "Default")
      (node (ref "IC1") (pin "57") (pinfunction "SCL1/RG2_57") (pintype "bidirectional"))
      (node (ref "JP4") (pin "6") (pinfunction "6_6") (pintype "bidirectional"))
    )
    (net (code "79") (name "RG3_SDA1") (class "Default")
      (node (ref "IC1") (pin "56") (pinfunction "SDA1/RG3_56") (pintype "bidirectional"))
      (node (ref "JP4") (pin "5") (pinfunction "5_5") (pintype "bidirectional"))
    )
    (net (code "80") (name "RG6_SCLK") (class "Default")
      (node (ref "IC1") (pin "10") (pinfunction "PMA5/SCK2/CN8/RG6_10") (pintype "bidirectional"))
      (node (ref "JP2") (pin "4") (pinfunction "4_4") (pintype "bidirectional"))
    )
    (net (code "81") (name "RG7_MISO") (class "Default")
      (node (ref "IC1") (pin "11") (pinfunction "PMA4/SDI2/CN9/RG7_11") (pintype "bidirectional"))
      (node (ref "JP2") (pin "8") (pinfunction "8_8") (pintype "bidirectional"))
    )
    (net (code "82") (name "RG8_MOSI") (class "Default")
      (node (ref "IC1") (pin "12") (pinfunction "PMA3/SDO2/CN10/RG8_12") (pintype "bidirectional"))
      (node (ref "JP2") (pin "5") (pinfunction "5_5") (pintype "bidirectional"))
    )
    (net (code "83") (name "RG9_CS") (class "Default")
      (node (ref "IC1") (pin "14") (pinfunction "PMA2/~{SS2/CN11/RG9}_14") (pintype "bidirectional"))
      (node (ref "JP2") (pin "7") (pinfunction "7_7") (pintype "bidirectional"))
    )
    (net (code "84") (name "RG15") (class "Default")
      (node (ref "IC1") (pin "1") (pinfunction "RG15_1") (pintype "bidirectional"))
      (node (ref "IC2") (pin "6") (pinfunction "ORG_6") (pintype "input"))
    )
    (net (code "85") (name "SER") (class "Default")
      (node (ref "IC1") (pin "59") (pinfunction "SDA2/RA3_59") (pintype "bidirectional"))
      (node (ref "X5") (pin "3") (pinfunction "S_3") (pintype "passive"))
    )
    (net (code "86") (name "SHIFT_EN") (class "Default")
      (node (ref "IC1") (pin "51") (pinfunction "U1TX/RF3_51") (pintype "bidirectional"))
      (node (ref "R19") (pin "1") (pinfunction "1_1") (pintype "passive"))
      (node (ref "X5") (pin "8") (pinfunction "S_8") (pintype "passive"))
    )
    (net (code "87") (name "SM_LED") (class "Default")
      (node (ref "IC1") (pin "28") (pinfunction "PMA7/VREF-/RA9_28") (pintype "bidirectional"))
      (node (ref "R5") (pin "1") (pinfunction "1_1") (pintype "passive"))
    )
    (net (code "88") (name "SRCLK") (class "Default")
      (node (ref "IC1") (pin "60") (pinfunction "TDI/RA4_60") (pintype "bidirectional"))
      (node (ref "X5") (pin "4") (pinfunction "S_4") (pintype "passive"))
    )
    (net (code "89") (name "SRCLR") (class "Default")
      (node (ref "IC1") (pin "91") (pinfunction "RA6_91") (pintype "bidirectional"))
      (node (ref "X5") (pin "5") (pinfunction "S_5") (pintype "passive"))
    )
    (net (code "90") (name "VDD") (class "Default")
      (node (ref "C11") (pin "1") (pinfunction "1_1") (pintype "passive"))
      (node (ref "C12") (pin "1") (pinfunction "1_1") (pintype "passive"))
      (node (ref "C13") (pin "1") (pinfunction "1_1") (pintype "passive"))
      (node (ref "C17") (pin "1") (pinfunction "1_1") (pintype "passive"))
      (node (ref "C20") (pin "1") (pinfunction "1_1") (pintype "passive"))
      (node (ref "C5") (pin "1") (pinfunction "1_1") (pintype "passive"))
      (node (ref "C6") (pin "1") (pinfunction "1_1") (pintype "passive"))
      (node (ref "IC1") (pin "16") (pinfunction "VDD_16") (pintype "power_in"))
      (node (ref "IC1") (pin "2") (pinfunction "VDD_2") (pintype "power_in"))
      (node (ref "IC1") (pin "30") (pinfunction "AVDD_30") (pintype "power_in"))
      (node (ref "IC1") (pin "37") (pinfunction "VDD_37") (pintype "power_in"))
      (node (ref "IC1") (pin "46") (pinfunction "VDD_46") (pintype "power_in"))
      (node (ref "IC1") (pin "62") (pinfunction "VDD_62") (pintype "power_in"))
      (node (ref "IC1") (pin "86") (pinfunction "ENVREG_86") (pintype "bidirectional"))
      (node (ref "IC2") (pin "8") (pinfunction "VCC_8") (pintype "power_in"))
      (node (ref "J12") (pin "5") (pinfunction "5_5") (pintype "passive"))
      (node (ref "JP12") (pin "2") (pinfunction "2_2") (pintype "bidirectional"))
      (node (ref "JP14") (pin "1") (pinfunction "1_1") (pintype "bidirectional"))
      (node (ref "JP15") (pin "1") (pinfunction "1_1") (pintype "bidirectional"))
      (node (ref "JP16") (pin "1") (pinfunction "1_1") (pintype "bidirectional"))
      (node (ref "JP4") (pin "8") (pinfunction "8_8") (pintype "bidirectional"))
      (node (ref "R13") (pin "2") (pinfunction "2_2") (pintype "passive"))
      (node (ref "R19") (pin "2") (pinfunction "2_2") (pintype "passive"))
      (node (ref "R3") (pin "2") (pinfunction "2_2") (pintype "passive"))
      (node (ref "R4") (pin "2") (pinfunction "2_2") (pintype "passive"))
      (node (ref "U1") (pin "20") (pinfunction "VCC_20") (pintype "power_in"))
      (node (ref "U2") (pin "5") (pinfunction "VOUT_5") (pintype "output"))
    )
    (net (code "91") (name "VIN_1") (class "Default")
      (node (ref "C1") (pin "1") (pinfunction "1_1") (pintype "passive"))
      (node (ref "D1") (pin "2") (pinfunction "A_2") (pintype "passive"))
      (node (ref "D2") (pin "1") (pinfunction "C_1") (pintype "passive"))
      (node (ref "IC1") (pin "20") (pinfunction "C1IN+/AN5/CN7/RB5_20") (pintype "bidirectional"))
      (node (ref "R1") (pin "1") (pinfunction "1_1") (pintype "passive"))
      (node (ref "R2") (pin "2") (pinfunction "S_2") (pintype "passive"))
    )
    (net (code "92") (name "VIN_2") (class "Default")
      (node (ref "C22") (pin "1") (pinfunction "1_1") (pintype "passive"))
      (node (ref "D4") (pin "2") (pinfunction "A_2") (pintype "passive"))
      (node (ref "D5") (pin "1") (pinfunction "C_1") (pintype "passive"))
      (node (ref "IC1") (pin "24") (pinfunction "PGC1/EMUC1/AN1/CN3/RB1_24") (pintype "bidirectional"))
      (node (ref "R16") (pin "1") (pinfunction "1_1") (pintype "passive"))
      (node (ref "R17") (pin "2") (pinfunction "S_2") (pintype "passive"))
    )
    (net (code "93") (name "VRR") (class "Default")
      (node (ref "C18") (pin "1") (pinfunction "1_1") (pintype "passive"))
      (node (ref "D1") (pin "1") (pinfunction "C_1") (pintype "passive"))
      (node (ref "D4") (pin "1") (pinfunction "C_1") (pintype "passive"))
      (node (ref "U3") (pin "5") (pinfunction "VOUT_5") (pintype "output"))
    )
    (net (code "94") (name "unconnected-(IC1-OSC1{slash}CLKI{slash}RC12-Pad63)") (class "Default")
      (node (ref "IC1") (pin "63") (pinfunction "OSC1/CLKI/RC12_63") (pintype "bidirectional"))
    )
    (net (code "95") (name "unconnected-(IC1-OSC2{slash}CLKO{slash}RC15-Pad64)") (class "Default")
      (node (ref "IC1") (pin "64") (pinfunction "OSC2/CLKO/RC15_64") (pintype "bidirectional"))
    )
    (net (code "96") (name "unconnected-(IC1-PMA0{slash}AN15{slash}OCFB{slash}CN12{slash}RB15-Pad44)") (class "Default")
      (node (ref "IC1") (pin "44") (pinfunction "PMA0/AN15/OCFB/CN12/RB15_44") (pintype "bidirectional"))
    )
    (net (code "97") (name "unconnected-(IC1-PMA1{slash}AN14{slash}RB14-Pad43)") (class "Default")
      (node (ref "IC1") (pin "43") (pinfunction "PMA1/AN14/RB14_43") (pintype "bidirectional"))
    )
    (net (code "98") (name "unconnected-(IC1-PMA6{slash}VREF+{slash}RA10-Pad29)") (class "Default")
      (node (ref "IC1") (pin "29") (pinfunction "PMA6/VREF+/RA10_29") (pintype "bidirectional"))
    )
    (net (code "99") (name "unconnected-(IC1-PMD1{slash}RE1-Pad94)") (class "Default")
      (node (ref "IC1") (pin "94") (pinfunction "PMD1/RE1_94") (pintype "bidirectional"))
    )
    (net (code "100") (name "unconnected-(IC1-PMD2{slash}RE2-Pad98)") (class "Default")
      (node (ref "IC1") (pin "98") (pinfunction "PMD2/RE2_98") (pintype "bidirectional"))
    )
    (net (code "101") (name "unconnected-(IC1-PMD6{slash}RE6-Pad4)") (class "Default")
      (node (ref "IC1") (pin "4") (pinfunction "PMD6/RE6_4") (pintype "bidirectional"))
    )
    (net (code "102") (name "unconnected-(IC1-PMD7{slash}RE7-Pad5)") (class "Default")
      (node (ref "IC1") (pin "5") (pinfunction "PMD7/RE7_5") (pintype "bidirectional"))
    )
    (net (code "103") (name "unconnected-(IC1-RF1-Pad88)") (class "Default")
      (node (ref "IC1") (pin "88") (pinfunction "RF1_88") (pintype "bidirectional"))
    )
    (net (code "104") (name "unconnected-(IC1-RG12-Pad96)") (class "Default")
      (node (ref "IC1") (pin "96") (pinfunction "RG12_96") (pintype "bidirectional"))
    )
    (net (code "105") (name "unconnected-(IC1-RG13-Pad97)") (class "Default")
      (node (ref "IC1") (pin "97") (pinfunction "RG13_97") (pintype "bidirectional"))
    )
    (net (code "106") (name "unconnected-(IC1-RG14-Pad95)") (class "Default")
      (node (ref "IC1") (pin "95") (pinfunction "RG14_95") (pintype "bidirectional"))
    )
    (net (code "107") (name "unconnected-(IC1-SOSCI{slash}CN1{slash}RC13-Pad73)") (class "Default")
      (node (ref "IC1") (pin "73") (pinfunction "SOSCI/CN1/RC13_73") (pintype "bidirectional"))
    )
    (net (code "108") (name "unconnected-(IC1-SOSCO{slash}T1CK{slash}CN0{slash}RC14-Pad74)") (class "Default")
      (node (ref "IC1") (pin "74") (pinfunction "SOSCO/T1CK/CN0/RC14_74") (pintype "bidirectional"))
    )
    (net (code "109") (name "unconnected-(IC2-NU-Pad7)") (class "Default")
      (node (ref "IC2") (pin "7") (pinfunction "NU_7") (pintype "passive"))
    )
    (net (code "110") (name "unconnected-(J12-Pad1)") (class "Default")
      (node (ref "J12") (pin "1") (pinfunction "1_1") (pintype "passive"))
    )
    (net (code "111") (name "unconnected-(R2-E-Pad3)") (class "Default")
      (node (ref "R2") (pin "3") (pinfunction "E_3") (pintype "passive"))
    )
    (net (code "112") (name "unconnected-(R17-E-Pad3)") (class "Default")
      (node (ref "R17") (pin "3") (pinfunction "E_3") (pintype "passive"))
    )
    (net (code "113") (name "unconnected-(RLY1B-O-Pad7)") (class "Default")
      (node (ref "RLY1") (pin "7") (pinfunction "O_7") (pintype "passive"))
    )
    (net (code "114") (name "unconnected-(RLY1C-O-Pad2)") (class "Default")
      (node (ref "RLY1") (pin "2") (pinfunction "O_2") (pintype "passive"))
    )
    (net (code "115") (name "unconnected-(RLY1C-P-Pad3)") (class "Default")
      (node (ref "RLY1") (pin "3") (pinfunction "P_3") (pintype "passive"))
    )
    (net (code "116") (name "unconnected-(RLY1C-S-Pad4)") (class "Default")
      (node (ref "RLY1") (pin "4") (pinfunction "S_4") (pintype "passive"))
    )
    (net (code "117") (name "unconnected-(U1-IN1-Pad2)") (class "Default")
      (node (ref "U1") (pin "2") (pinfunction "IN1_2") (pintype "bidirectional"))
    )
    (net (code "118") (name "unconnected-(U1-IN6-Pad7)") (class "Default")
      (node (ref "U1") (pin "7") (pinfunction "IN6_7") (pintype "bidirectional"))
    )
    (net (code "119") (name "unconnected-(U1-IN7-Pad8)") (class "Default")
      (node (ref "U1") (pin "8") (pinfunction "IN7_8") (pintype "bidirectional"))
    )
    (net (code "120") (name "unconnected-(U1-IN8-Pad9)") (class "Default")
      (node (ref "U1") (pin "9") (pinfunction "IN8_9") (pintype "bidirectional"))
    )
    (net (code "121") (name "unconnected-(U1-OUT1-Pad19)") (class "Default")
      (node (ref "U1") (pin "19") (pinfunction "OUT1_19") (pintype "output"))
    )
    (net (code "122") (name "unconnected-(U1-OUT6-Pad14)") (class "Default")
      (node (ref "U1") (pin "14") (pinfunction "OUT6_14") (pintype "output"))
    )
    (net (code "123") (name "unconnected-(U1-OUT7-Pad13)") (class "Default")
      (node (ref "U1") (pin "13") (pinfunction "OUT7_13") (pintype "output"))
    )
    (net (code "124") (name "unconnected-(U1-OUT8-Pad12)") (class "Default")
      (node (ref "U1") (pin "12") (pinfunction "OUT8_12") (pintype "output"))
    )
    (net (code "125") (name "unconnected-(U1-~{CH}-Pad11)") (class "Default")
      (node (ref "U1") (pin "11") (pinfunction "~{CH}_11") (pintype "output"))
    )
  )
)
